# MCU.net
KiCad netlist of a schematic drawn in Altium Designer
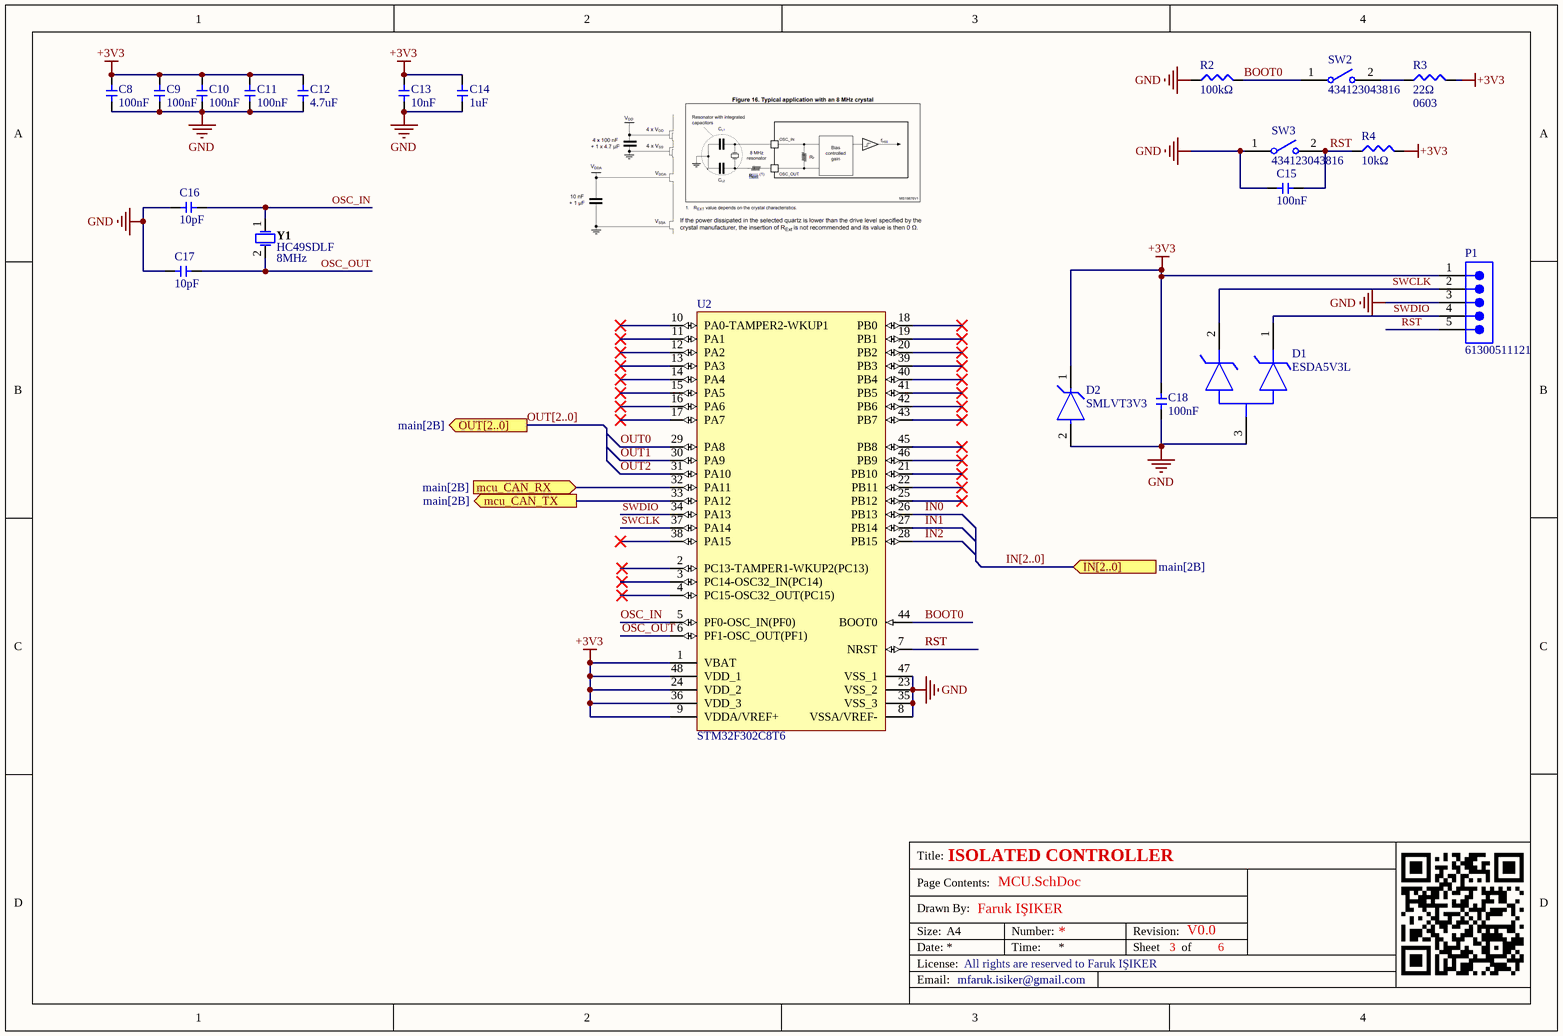
[diagram p0: MCU.SchDoc]

(export (version "E")
  (design (tool "Eeschema 10.0.6"))
  (components
    (comp (ref "C8")
      (value "100nF")
      (footprint "0603_cap")
      (fields (field (name "Comment") "0603_100nF"))
      (libsource (lib "generic") (part "0603_100nF"))
    )
    (comp (ref "C9")
      (value "100nF")
      (footprint "0603_cap")
      (fields (field (name "Comment") "0603_100nF"))
      (libsource (lib "generic") (part "0603_100nF"))
    )
    (comp (ref "C10")
      (value "100nF")
      (footprint "0603_cap")
      (fields (field (name "Comment") "0603_100nF"))
      (libsource (lib "generic") (part "0603_100nF"))
    )
    (comp (ref "C11")
      (value "100nF")
      (footprint "0603_cap")
      (fields (field (name "Comment") "0603_100nF"))
      (libsource (lib "generic") (part "0603_100nF"))
    )
    (comp (ref "C12")
      (value "4.7uF")
      (footprint "0603_cap")
      (fields (field (name "Comment") "0603_4.7uF"))
      (libsource (lib "generic") (part "0603_4.7uF"))
    )
    (comp (ref "C13")
      (value "10nF")
      (footprint "0603_cap")
      (fields (field (name "Comment") "0603_10nF"))
      (libsource (lib "generic") (part "0603_10nF"))
    )
    (comp (ref "C14")
      (value "1uF")
      (footprint "0603_cap")
      (fields (field (name "Comment") "0603_1uF"))
      (libsource (lib "generic") (part "0603_1uF"))
    )
    (comp (ref "C15")
      (value "100nF")
      (footprint "0603_cap")
      (fields (field (name "Comment") "0603_100nF"))
      (libsource (lib "generic") (part "0603_100nF"))
    )
    (comp (ref "C16")
      (value "10pF")
      (footprint "0603_cap")
      (fields (field (name "Comment") "0603_10pF"))
      (libsource (lib "generic") (part "0603_10pF"))
    )
    (comp (ref "C17")
      (value "10pF")
      (footprint "0603_cap")
      (fields (field (name "Comment") "0603_10pF"))
      (libsource (lib "generic") (part "0603_10pF"))
    )
    (comp (ref "C18")
      (value "100nF")
      (footprint "0603_cap")
      (fields (field (name "Comment") "0603_100nF"))
      (libsource (lib "generic") (part "0603_100nF"))
    )
    (comp (ref "D1")
      (value "ESDA5V3L")
      (footprint "FP-SOT23-3L-0053390-MFG")
      (description "TVS DIODE 3V SOT23-3")
      (fields
        (field (name "OCTOPART") "https://octopart.com/esda5v3l-stmicroelectronics-347708")
        (field (name "MANUFACTURER") "STMicroelectronics")
      )
      (libsource (lib "Altium Content Vault") (part "852f986ac35c0497f1e372686d5e728"))
    )
    (comp (ref "D2")
      (value "SMLVT3V3")
      (footprint "FP-SMB-MFG")
      (description "TVS DIODE 3.3V 10.3V SMB")
      (fields
        (field (name "MANUFACTURER") "STMicroelectronics")
        (field (name "OCTOPART") "https://octopart.com/smlvt3v3-stmicroelectronics-347049")
      )
      (libsource (lib "Altium Content Vault") (part "7ddec9f632b8482e96f7745d0fbdf39"))
    )
    (comp (ref "P1")
      (value "61300511121")
      (footprint "61300511121")
      (libsource (lib "Altium Content Vault") (part "Header_Male_1R_05P"))
    )
    (comp (ref "R2")
      (value "100kΩ")
      (footprint "0603-smd")
      (fields (field (name "POWER") "W") (field (name "Comment") "0603_100K"))
      (libsource (lib "generic") (part "0603_100K"))
    )
    (comp (ref "R3")
      (value "22Ω")
      (footprint "0603-smd")
      (fields (field (name "POWER") "W") (field (name "PACKAGE") "0603") (field (name "Comment") "0603_22R"))
      (libsource (lib "generic") (part "0603_22R"))
    )
    (comp (ref "R4")
      (value "10kΩ")
      (footprint "0603-smd")
      (fields (field (name "POWER") "W") (field (name "Comment") "0603_10K"))
      (libsource (lib "generic") (part "0603_10K"))
    )
    (comp (ref "SW2")
      (value "434123043816")
      (footprint "WS-TASV_L6W3.5H4.3_4341x30438x6")
      (libsource (lib "Altium Content Vault") (part "SPST-NO_2P"))
    )
    (comp (ref "SW3")
      (value "434123043816")
      (footprint "WS-TASV_L6W3.5H4.3_4341x30438x6")
      (libsource (lib "Altium Content Vault") (part "SPST-NO_2P"))
    )
    (comp (ref "U2")
      (value "STM32F302C8T6")
      (footprint "STM-LQFP48_L")
      (libsource (lib "Altium Content Vault") (part "MC-ARM-STM32F30X-LQFP48"))
    )
    (comp (ref "Y1")
      (value "FOXSDLF/080-20")
      (footprint "FOX-HC49SDLF_V")
      (description "Resistance Weld Crystal, 8 MHz, +/- 30 ppm, -20 to 70 degC, 2-Pin SMD, RoHS, Tape and Reel")
      (fields
        (field (name "MANUFACTURER") "FOX Electronics")
        (field (name "PACKAGE REFERENCE") "HC49SDLF")
        (field (name "FREQUENCY") "8MHz")
        (field (name "TOLERANCE") "50ppm")
      )
      (libsource (lib "Altium Content Vault") (part "XTAL-1-2-2"))
    )
  )
  (nets
    (net (code "1") (name "+3V3") (class "Default")
      (node (ref "C10") (pin "2") (pinfunction "2_2") (pintype "passive"))
      (node (ref "C11") (pin "2") (pinfunction "2_2") (pintype "passive"))
      (node (ref "C12") (pin "2") (pinfunction "2_2") (pintype "passive"))
      (node (ref "C13") (pin "2") (pinfunction "2_2") (pintype "passive"))
      (node (ref "C14") (pin "2") (pinfunction "2_2") (pintype "passive"))
      (node (ref "C18") (pin "2") (pinfunction "2_2") (pintype "passive"))
      (node (ref "C8") (pin "2") (pinfunction "2_2") (pintype "passive"))
      (node (ref "C9") (pin "2") (pinfunction "2_2") (pintype "passive"))
      (node (ref "D2") (pin "1") (pinfunction "K_1") (pintype "passive"))
      (node (ref "P1") (pin "1") (pinfunction "1_1") (pintype "passive"))
      (node (ref "R3") (pin "2") (pinfunction "2_2") (pintype "passive"))
      (node (ref "R4") (pin "1") (pinfunction "1_1") (pintype "passive"))
      (node (ref "U2") (pin "1") (pinfunction "VBAT_1") (pintype "power_in"))
      (node (ref "U2") (pin "24") (pinfunction "VDD_2_24") (pintype "power_in"))
      (node (ref "U2") (pin "36") (pinfunction "VDD_3_36") (pintype "power_in"))
      (node (ref "U2") (pin "48") (pinfunction "VDD_1_48") (pintype "power_in"))
      (node (ref "U2") (pin "9") (pinfunction "VDDA/VREF+_9") (pintype "power_in"))
    )
    (net (code "2") (name "/BOOT0") (class "Default")
      (node (ref "R2") (pin "1") (pinfunction "1_1") (pintype "passive"))
      (node (ref "SW2") (pin "1") (pinfunction "1_1") (pintype "passive"))
      (node (ref "U2") (pin "44") (pinfunction "BOOT0_44") (pintype "input"))
    )
    (net (code "3") (name "/IN0") (class "Default")
      (node (ref "U2") (pin "26") (pinfunction "PB13_26") (pintype "bidirectional"))
    )
    (net (code "4") (name "/IN1") (class "Default")
      (node (ref "U2") (pin "27") (pinfunction "PB14_27") (pintype "bidirectional"))
    )
    (net (code "5") (name "/IN2") (class "Default")
      (node (ref "U2") (pin "28") (pinfunction "PB15_28") (pintype "bidirectional"))
    )
    (net (code "7") (name "/OSC_IN") (class "Default")
      (node (ref "C16") (pin "2") (pinfunction "2_2") (pintype "passive"))
      (node (ref "U2") (pin "5") (pinfunction "PF0-OSC_IN(PF0)_5") (pintype "bidirectional"))
      (node (ref "Y1") (pin "1") (pinfunction "1_1") (pintype "passive"))
    )
    (net (code "8") (name "/OSC_OUT") (class "Default")
      (node (ref "C17") (pin "2") (pinfunction "2_2") (pintype "passive"))
      (node (ref "U2") (pin "6") (pinfunction "PF1-OSC_OUT(PF1)_6") (pintype "bidirectional"))
      (node (ref "Y1") (pin "2") (pinfunction "2_2") (pintype "passive"))
    )
    (net (code "9") (name "/OUT0") (class "Default")
      (node (ref "U2") (pin "29") (pinfunction "PA8_29") (pintype "bidirectional"))
    )
    (net (code "10") (name "/OUT1") (class "Default")
      (node (ref "U2") (pin "30") (pinfunction "PA9_30") (pintype "bidirectional"))
    )
    (net (code "11") (name "/OUT2") (class "Default")
      (node (ref "U2") (pin "31") (pinfunction "PA10_31") (pintype "bidirectional"))
    )
    (net (code "13") (name "/RST") (class "Default")
      (node (ref "C15") (pin "2") (pinfunction "2_2") (pintype "passive"))
      (node (ref "P1") (pin "5") (pinfunction "5_5") (pintype "passive"))
      (node (ref "R4") (pin "2") (pinfunction "2_2") (pintype "passive"))
      (node (ref "SW3") (pin "2") (pinfunction "2_2") (pintype "passive"))
      (node (ref "U2") (pin "7") (pinfunction "NRST_7") (pintype "bidirectional"))
    )
    (net (code "14") (name "/SWCLK") (class "Default")
      (node (ref "D1") (pin "2") (pinfunction "2_CATHODE_2") (pintype "passive"))
      (node (ref "P1") (pin "2") (pinfunction "2_2") (pintype "passive"))
      (node (ref "U2") (pin "37") (pinfunction "PA14_37") (pintype "bidirectional"))
    )
    (net (code "15") (name "/SWDIO") (class "Default")
      (node (ref "D1") (pin "1") (pinfunction "1_CATHODE_1") (pintype "passive"))
      (node (ref "P1") (pin "4") (pinfunction "4_4") (pintype "passive"))
      (node (ref "U2") (pin "34") (pinfunction "PA13_34") (pintype "bidirectional"))
    )
    (net (code "16") (name "/mcu_CAN_RX") (class "Default")
      (node (ref "U2") (pin "32") (pinfunction "PA11_32") (pintype "bidirectional"))
    )
    (net (code "17") (name "/mcu_CAN_TX") (class "Default")
      (node (ref "U2") (pin "33") (pinfunction "PA12_33") (pintype "bidirectional"))
    )
    (net (code "18") (name "GND") (class "Default")
      (node (ref "C10") (pin "1") (pinfunction "1_1") (pintype "passive"))
      (node (ref "C11") (pin "1") (pinfunction "1_1") (pintype "passive"))
      (node (ref "C12") (pin "1") (pinfunction "1_1") (pintype "passive"))
      (node (ref "C13") (pin "1") (pinfunction "1_1") (pintype "passive"))
      (node (ref "C14") (pin "1") (pinfunction "1_1") (pintype "passive"))
      (node (ref "C15") (pin "1") (pinfunction "1_1") (pintype "passive"))
      (node (ref "C16") (pin "1") (pinfunction "1_1") (pintype "passive"))
      (node (ref "C17") (pin "1") (pinfunction "1_1") (pintype "passive"))
      (node (ref "C18") (pin "1") (pinfunction "1_1") (pintype "passive"))
      (node (ref "C8") (pin "1") (pinfunction "1_1") (pintype "passive"))
      (node (ref "C9") (pin "1") (pinfunction "1_1") (pintype "passive"))
      (node (ref "D1") (pin "3") (pinfunction "COMMON_ANODE_3") (pintype "passive"))
      (node (ref "D2") (pin "2") (pinfunction "A_2") (pintype "passive"))
      (node (ref "P1") (pin "3") (pinfunction "3_3") (pintype "passive"))
      (node (ref "R2") (pin "2") (pinfunction "2_2") (pintype "passive"))
      (node (ref "SW3") (pin "1") (pinfunction "1_1") (pintype "passive"))
      (node (ref "U2") (pin "23") (pinfunction "VSS_2_23") (pintype "power_in"))
      (node (ref "U2") (pin "35") (pinfunction "VSS_3_35") (pintype "power_in"))
      (node (ref "U2") (pin "47") (pinfunction "VSS_1_47") (pintype "power_in"))
      (node (ref "U2") (pin "8") (pinfunction "VSSA/VREF-_8") (pintype "power_in"))
    )
    (net (code "19") (name "Net-(R3-Pad1)") (class "Default")
      (node (ref "R3") (pin "1") (pinfunction "1_1") (pintype "passive"))
      (node (ref "SW2") (pin "2") (pinfunction "2_2") (pintype "passive"))
    )
    (net (code "20") (name "unconnected-(U2-PA0-TAMPER2-WKUP1-Pad10)") (class "Default")
      (node (ref "U2") (pin "10") (pinfunction "PA0-TAMPER2-WKUP1_10") (pintype "bidirectional+no_connect"))
    )
    (net (code "21") (name "unconnected-(U2-PA1-Pad11)") (class "Default")
      (node (ref "U2") (pin "11") (pinfunction "PA1_11") (pintype "bidirectional+no_connect"))
    )
    (net (code "22") (name "unconnected-(U2-PA2-Pad12)") (class "Default")
      (node (ref "U2") (pin "12") (pinfunction "PA2_12") (pintype "bidirectional+no_connect"))
    )
    (net (code "23") (name "unconnected-(U2-PA3-Pad13)") (class "Default")
      (node (ref "U2") (pin "13") (pinfunction "PA3_13") (pintype "bidirectional+no_connect"))
    )
    (net (code "24") (name "unconnected-(U2-PA4-Pad14)") (class "Default")
      (node (ref "U2") (pin "14") (pinfunction "PA4_14") (pintype "bidirectional+no_connect"))
    )
    (net (code "25") (name "unconnected-(U2-PA5-Pad15)") (class "Default")
      (node (ref "U2") (pin "15") (pinfunction "PA5_15") (pintype "bidirectional+no_connect"))
    )
    (net (code "26") (name "unconnected-(U2-PA6-Pad16)") (class "Default")
      (node (ref "U2") (pin "16") (pinfunction "PA6_16") (pintype "bidirectional+no_connect"))
    )
    (net (code "27") (name "unconnected-(U2-PA7-Pad17)") (class "Default")
      (node (ref "U2") (pin "17") (pinfunction "PA7_17") (pintype "bidirectional+no_connect"))
    )
    (net (code "28") (name "unconnected-(U2-PA15-Pad38)") (class "Default")
      (node (ref "U2") (pin "38") (pinfunction "PA15_38") (pintype "bidirectional+no_connect"))
    )
    (net (code "29") (name "unconnected-(U2-PB0-Pad18)") (class "Default")
      (node (ref "U2") (pin "18") (pinfunction "PB0_18") (pintype "bidirectional+no_connect"))
    )
    (net (code "30") (name "unconnected-(U2-PB1-Pad19)") (class "Default")
      (node (ref "U2") (pin "19") (pinfunction "PB1_19") (pintype "bidirectional+no_connect"))
    )
    (net (code "31") (name "unconnected-(U2-PB2-Pad20)") (class "Default")
      (node (ref "U2") (pin "20") (pinfunction "PB2_20") (pintype "bidirectional+no_connect"))
    )
    (net (code "32") (name "unconnected-(U2-PB3-Pad39)") (class "Default")
      (node (ref "U2") (pin "39") (pinfunction "PB3_39") (pintype "bidirectional+no_connect"))
    )
    (net (code "33") (name "unconnected-(U2-PB4-Pad40)") (class "Default")
      (node (ref "U2") (pin "40") (pinfunction "PB4_40") (pintype "bidirectional+no_connect"))
    )
    (net (code "34") (name "unconnected-(U2-PB5-Pad41)") (class "Default")
      (node (ref "U2") (pin "41") (pinfunction "PB5_41") (pintype "bidirectional+no_connect"))
    )
    (net (code "35") (name "unconnected-(U2-PB6-Pad42)") (class "Default")
      (node (ref "U2") (pin "42") (pinfunction "PB6_42") (pintype "bidirectional+no_connect"))
    )
    (net (code "36") (name "unconnected-(U2-PB7-Pad43)") (class "Default")
      (node (ref "U2") (pin "43") (pinfunction "PB7_43") (pintype "bidirectional+no_connect"))
    )
    (net (code "37") (name "unconnected-(U2-PB8-Pad45)") (class "Default")
      (node (ref "U2") (pin "45") (pinfunction "PB8_45") (pintype "bidirectional+no_connect"))
    )
    (net (code "38") (name "unconnected-(U2-PB9-Pad46)") (class "Default")
      (node (ref "U2") (pin "46") (pinfunction "PB9_46") (pintype "bidirectional+no_connect"))
    )
    (net (code "39") (name "unconnected-(U2-PB10-Pad21)") (class "Default")
      (node (ref "U2") (pin "21") (pinfunction "PB10_21") (pintype "bidirectional+no_connect"))
    )
    (net (code "40") (name "unconnected-(U2-PB11-Pad22)") (class "Default")
      (node (ref "U2") (pin "22") (pinfunction "PB11_22") (pintype "bidirectional+no_connect"))
    )
    (net (code "41") (name "unconnected-(U2-PB12-Pad25)") (class "Default")
      (node (ref "U2") (pin "25") (pinfunction "PB12_25") (pintype "bidirectional+no_connect"))
    )
    (net (code "42") (name "unconnected-(U2-PC13-TAMPER1-WKUP2(PC13)-Pad2)") (class "Default")
      (node (ref "U2") (pin "2") (pinfunction "PC13-TAMPER1-WKUP2(PC13)_2") (pintype "bidirectional"))
    )
    (net (code "43") (name "unconnected-(U2-PC14-OSC32_IN(PC14)-Pad3)") (class "Default")
      (node (ref "U2") (pin "3") (pinfunction "PC14-OSC32_IN(PC14)_3") (pintype "bidirectional"))
    )
    (net (code "44") (name "unconnected-(U2-PC15-OSC32_OUT(PC15)-Pad4)") (class "Default")
      (node (ref "U2") (pin "4") (pinfunction "PC15-OSC32_OUT(PC15)_4") (pintype "bidirectional"))
    )
  )
)
